# SMART4.net
KiCad netlist of a schematic drawn in EAGLE
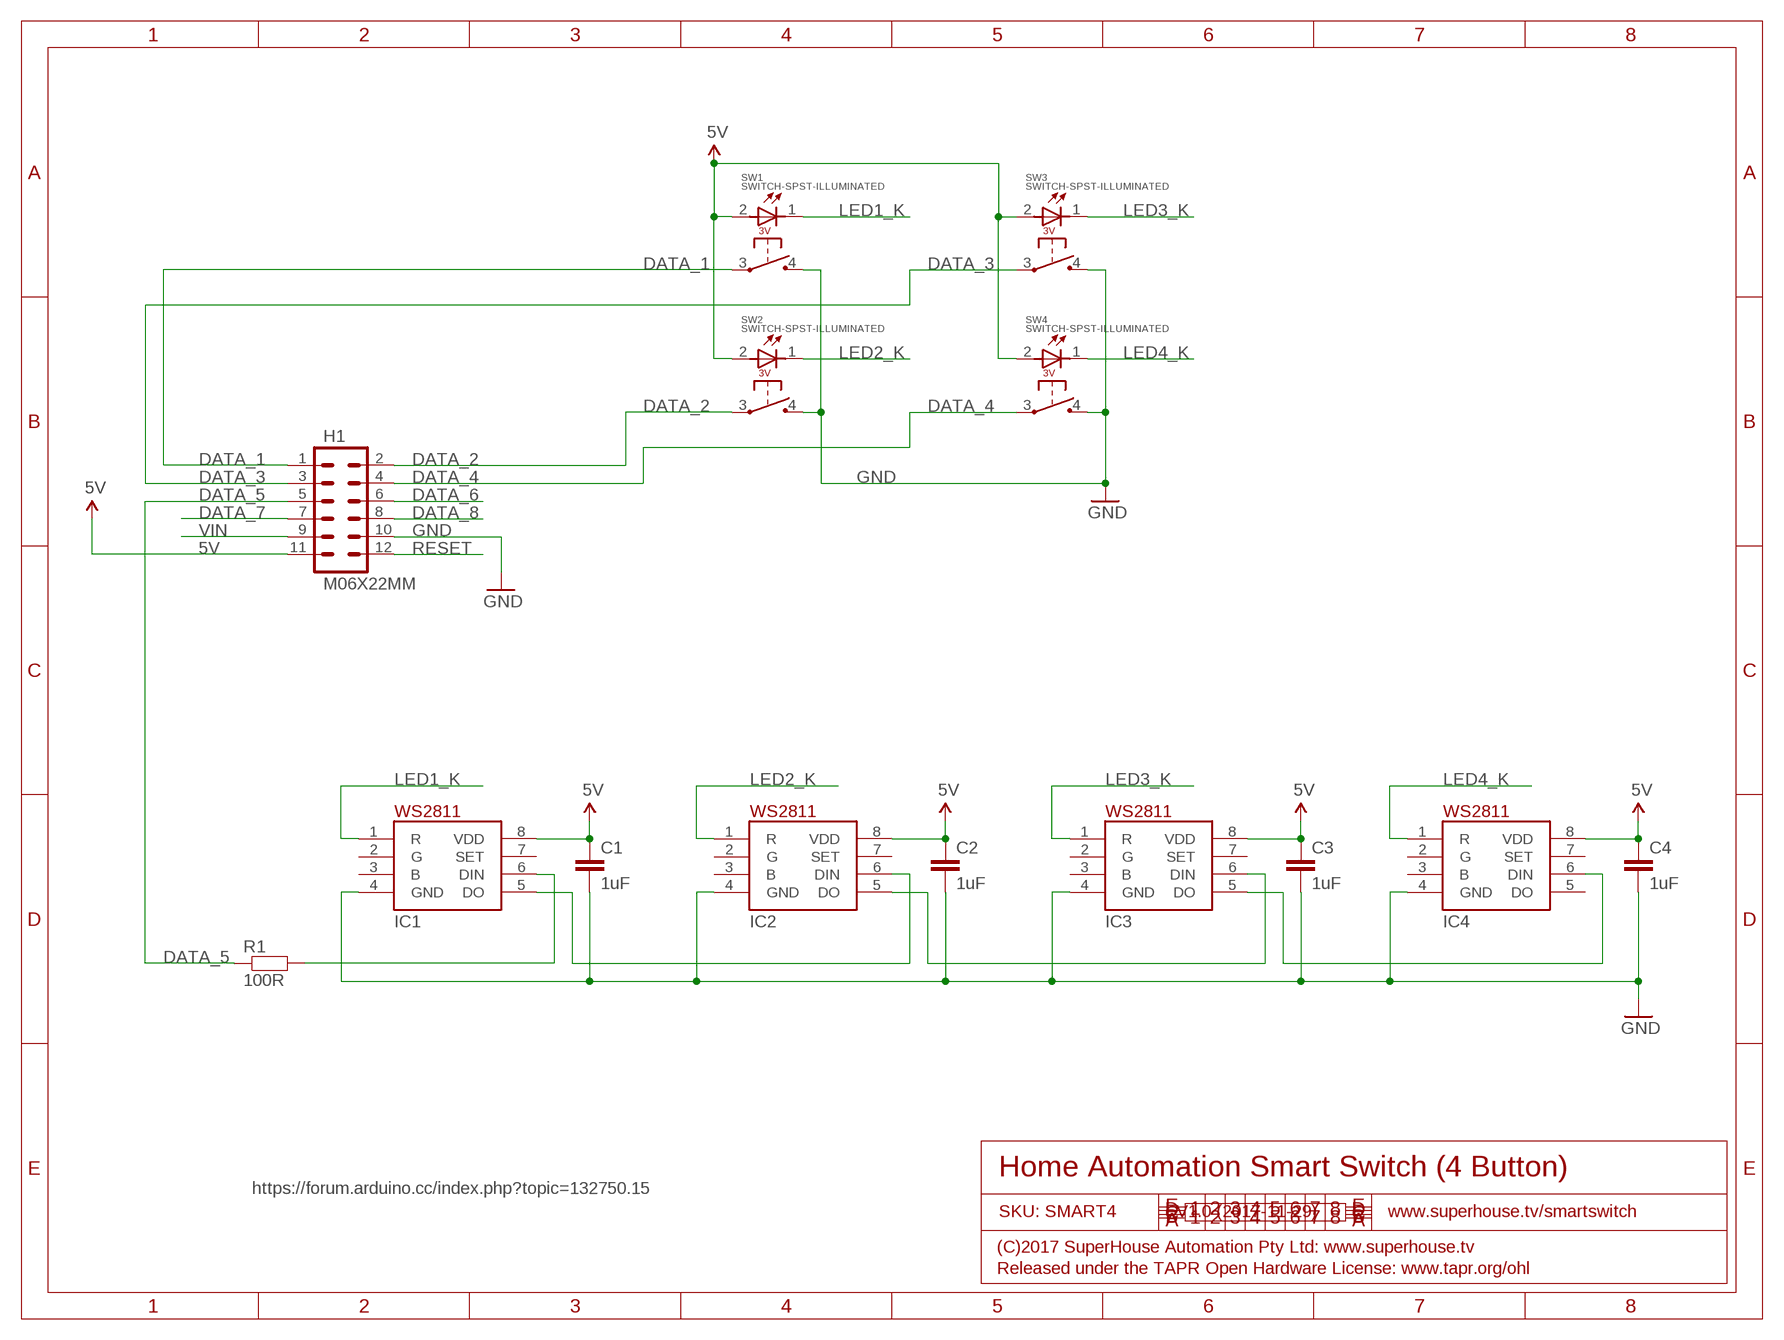
[diagram p0: schematic, sheet 1]

(export (version "E")
  (design (tool "Eeschema 10.0.6"))
  (components
    (comp (ref "C1")
      (value "1uF")
      (footprint "eagle-import:0603")
      (libsource (lib "eagle-import") (part "CAP0603"))
    )
    (comp (ref "C2")
      (value "1uF")
      (footprint "eagle-import:0603")
      (libsource (lib "eagle-import") (part "CAP0603"))
    )
    (comp (ref "C3")
      (value "1uF")
      (footprint "eagle-import:0603")
      (libsource (lib "eagle-import") (part "CAP0603"))
    )
    (comp (ref "C4")
      (value "1uF")
      (footprint "eagle-import:0603")
      (libsource (lib "eagle-import") (part "CAP0603"))
    )
    (comp (ref "H1")
      (value "M06X22MM")
      (footprint "eagle-import:2X6-2MM")
      (libsource (lib "eagle-import") (part "M06X22MM"))
    )
    (comp (ref "IC1")
      (value "WS2811-SOP8")
      (footprint "eagle-import:SO08-SKINNYPADS")
      (libsource (lib "eagle-import") (part "WS2811-SOP8"))
    )
    (comp (ref "IC2")
      (value "WS2811-SOP8")
      (footprint "eagle-import:SO08-SKINNYPADS")
      (libsource (lib "eagle-import") (part "WS2811-SOP8"))
    )
    (comp (ref "IC3")
      (value "WS2811-SOP8")
      (footprint "eagle-import:SO08-SKINNYPADS")
      (libsource (lib "eagle-import") (part "WS2811-SOP8"))
    )
    (comp (ref "IC4")
      (value "WS2811-SOP8")
      (footprint "eagle-import:SO08-SKINNYPADS")
      (libsource (lib "eagle-import") (part "WS2811-SOP8"))
    )
    (comp (ref "R1")
      (value "100R")
      (footprint "eagle-import:0603")
      (libsource (lib "eagle-import") (part "RESISTOR0603"))
    )
    (comp (ref "SW1")
      (value "SWITCH-SPST-ILLUMINATED")
      (footprint "eagle-import:SWITCH-SPST-ILLUMINATED")
      (libsource (lib "eagle-import") (part "SWITCH-SPST-ILLUMINATED"))
    )
    (comp (ref "SW2")
      (value "SWITCH-SPST-ILLUMINATED")
      (footprint "eagle-import:SWITCH-SPST-ILLUMINATED")
      (libsource (lib "eagle-import") (part "SWITCH-SPST-ILLUMINATED"))
    )
    (comp (ref "SW3")
      (value "SWITCH-SPST-ILLUMINATED")
      (footprint "eagle-import:SWITCH-SPST-ILLUMINATED")
      (libsource (lib "eagle-import") (part "SWITCH-SPST-ILLUMINATED"))
    )
    (comp (ref "SW4")
      (value "SWITCH-SPST-ILLUMINATED")
      (footprint "eagle-import:SWITCH-SPST-ILLUMINATED")
      (libsource (lib "eagle-import") (part "SWITCH-SPST-ILLUMINATED"))
    )
  )
  (nets
    (net (code "1") (name "/DATA_1") (class "Default")
      (node (ref "H1") (pin "1") (pinfunction "1_1") (pintype "passive"))
      (node (ref "SW1") (pin "3") (pinfunction "COM_3") (pintype "passive"))
    )
    (net (code "2") (name "/DATA_2") (class "Default")
      (node (ref "H1") (pin "2") (pinfunction "2_2") (pintype "passive"))
      (node (ref "SW2") (pin "3") (pinfunction "COM_3") (pintype "passive"))
    )
    (net (code "3") (name "/DATA_3") (class "Default")
      (node (ref "H1") (pin "3") (pinfunction "3_3") (pintype "passive"))
      (node (ref "SW3") (pin "3") (pinfunction "COM_3") (pintype "passive"))
    )
    (net (code "4") (name "/DATA_4") (class "Default")
      (node (ref "H1") (pin "4") (pinfunction "4_4") (pintype "passive"))
      (node (ref "SW4") (pin "3") (pinfunction "COM_3") (pintype "passive"))
    )
    (net (code "5") (name "/DATA_5") (class "Default")
      (node (ref "H1") (pin "5") (pinfunction "5_5") (pintype "passive"))
      (node (ref "R1") (pin "1") (pinfunction "1_1") (pintype "passive"))
    )
    (net (code "6") (name "/DATA_6") (class "Default")
      (node (ref "H1") (pin "6") (pinfunction "6_6") (pintype "passive"))
    )
    (net (code "7") (name "/DATA_7") (class "Default")
      (node (ref "H1") (pin "7") (pinfunction "7_7") (pintype "passive"))
    )
    (net (code "8") (name "/DATA_8") (class "Default")
      (node (ref "H1") (pin "8") (pinfunction "8_8") (pintype "passive"))
    )
    (net (code "9") (name "/LED1_K") (class "Default")
      (node (ref "IC1") (pin "1") (pinfunction "R_1") (pintype "open_collector"))
      (node (ref "SW1") (pin "1") (pinfunction "-_1") (pintype "passive"))
    )
    (net (code "10") (name "/LED2_K") (class "Default")
      (node (ref "IC2") (pin "1") (pinfunction "R_1") (pintype "open_collector"))
      (node (ref "SW2") (pin "1") (pinfunction "-_1") (pintype "passive"))
    )
    (net (code "11") (name "/LED3_K") (class "Default")
      (node (ref "IC3") (pin "1") (pinfunction "R_1") (pintype "open_collector"))
      (node (ref "SW3") (pin "1") (pinfunction "-_1") (pintype "passive"))
    )
    (net (code "12") (name "/LED4_K") (class "Default")
      (node (ref "IC4") (pin "1") (pinfunction "R_1") (pintype "open_collector"))
      (node (ref "SW4") (pin "1") (pinfunction "-_1") (pintype "passive"))
    )
    (net (code "13") (name "/RESET") (class "Default")
      (node (ref "H1") (pin "12") (pinfunction "12_12") (pintype "passive"))
    )
    (net (code "14") (name "/VIN") (class "Default")
      (node (ref "H1") (pin "9") (pinfunction "9_9") (pintype "passive"))
    )
    (net (code "15") (name "5V") (class "Default")
      (node (ref "C1") (pin "1") (pinfunction "1_1") (pintype "passive"))
      (node (ref "C2") (pin "1") (pinfunction "1_1") (pintype "passive"))
      (node (ref "C3") (pin "1") (pinfunction "1_1") (pintype "passive"))
      (node (ref "C4") (pin "1") (pinfunction "1_1") (pintype "passive"))
      (node (ref "H1") (pin "11") (pinfunction "11_11") (pintype "passive"))
      (node (ref "IC1") (pin "8") (pinfunction "VDD_8") (pintype "power_in"))
      (node (ref "IC2") (pin "8") (pinfunction "VDD_8") (pintype "power_in"))
      (node (ref "IC3") (pin "8") (pinfunction "VDD_8") (pintype "power_in"))
      (node (ref "IC4") (pin "8") (pinfunction "VDD_8") (pintype "power_in"))
      (node (ref "SW1") (pin "2") (pinfunction "+_2") (pintype "passive"))
      (node (ref "SW2") (pin "2") (pinfunction "+_2") (pintype "passive"))
      (node (ref "SW3") (pin "2") (pinfunction "+_2") (pintype "passive"))
      (node (ref "SW4") (pin "2") (pinfunction "+_2") (pintype "passive"))
    )
    (net (code "16") (name "GND") (class "Default")
      (node (ref "C1") (pin "2") (pinfunction "2_2") (pintype "passive"))
      (node (ref "C2") (pin "2") (pinfunction "2_2") (pintype "passive"))
      (node (ref "C3") (pin "2") (pinfunction "2_2") (pintype "passive"))
      (node (ref "C4") (pin "2") (pinfunction "2_2") (pintype "passive"))
      (node (ref "H1") (pin "10") (pinfunction "10_10") (pintype "passive"))
      (node (ref "IC1") (pin "4") (pinfunction "GND_4") (pintype "power_in"))
      (node (ref "IC2") (pin "4") (pinfunction "GND_4") (pintype "power_in"))
      (node (ref "IC3") (pin "4") (pinfunction "GND_4") (pintype "power_in"))
      (node (ref "IC4") (pin "4") (pinfunction "GND_4") (pintype "power_in"))
      (node (ref "SW1") (pin "4") (pinfunction "NO_4") (pintype "passive"))
      (node (ref "SW2") (pin "4") (pinfunction "NO_4") (pintype "passive"))
      (node (ref "SW3") (pin "4") (pinfunction "NO_4") (pintype "passive"))
      (node (ref "SW4") (pin "4") (pinfunction "NO_4") (pintype "passive"))
    )
    (net (code "17") (name "Net-(IC1-DIN)") (class "Default")
      (node (ref "IC1") (pin "6") (pinfunction "DIN_6") (pintype "input"))
      (node (ref "R1") (pin "2") (pinfunction "2_2") (pintype "passive"))
    )
    (net (code "18") (name "Net-(IC1-DO)") (class "Default")
      (node (ref "IC1") (pin "5") (pinfunction "DO_5") (pintype "output"))
      (node (ref "IC2") (pin "6") (pinfunction "DIN_6") (pintype "input"))
    )
    (net (code "19") (name "Net-(IC2-DO)") (class "Default")
      (node (ref "IC2") (pin "5") (pinfunction "DO_5") (pintype "output"))
      (node (ref "IC3") (pin "6") (pinfunction "DIN_6") (pintype "input"))
    )
    (net (code "20") (name "Net-(IC3-DO)") (class "Default")
      (node (ref "IC3") (pin "5") (pinfunction "DO_5") (pintype "output"))
      (node (ref "IC4") (pin "6") (pinfunction "DIN_6") (pintype "input"))
    )
    (net (code "21") (name "unconnected-(IC1-B-Pad3)") (class "Default")
      (node (ref "IC1") (pin "3") (pinfunction "B_3") (pintype "open_collector"))
    )
    (net (code "22") (name "unconnected-(IC1-G-Pad2)") (class "Default")
      (node (ref "IC1") (pin "2") (pinfunction "G_2") (pintype "open_collector"))
    )
    (net (code "23") (name "unconnected-(IC1-SET-Pad7)") (class "Default")
      (node (ref "IC1") (pin "7") (pinfunction "SET_7") (pintype "input"))
    )
    (net (code "24") (name "unconnected-(IC2-B-Pad3)") (class "Default")
      (node (ref "IC2") (pin "3") (pinfunction "B_3") (pintype "open_collector"))
    )
    (net (code "25") (name "unconnected-(IC2-G-Pad2)") (class "Default")
      (node (ref "IC2") (pin "2") (pinfunction "G_2") (pintype "open_collector"))
    )
    (net (code "26") (name "unconnected-(IC2-SET-Pad7)") (class "Default")
      (node (ref "IC2") (pin "7") (pinfunction "SET_7") (pintype "input"))
    )
    (net (code "27") (name "unconnected-(IC3-B-Pad3)") (class "Default")
      (node (ref "IC3") (pin "3") (pinfunction "B_3") (pintype "open_collector"))
    )
    (net (code "28") (name "unconnected-(IC3-G-Pad2)") (class "Default")
      (node (ref "IC3") (pin "2") (pinfunction "G_2") (pintype "open_collector"))
    )
    (net (code "29") (name "unconnected-(IC3-SET-Pad7)") (class "Default")
      (node (ref "IC3") (pin "7") (pinfunction "SET_7") (pintype "input"))
    )
    (net (code "30") (name "unconnected-(IC4-B-Pad3)") (class "Default")
      (node (ref "IC4") (pin "3") (pinfunction "B_3") (pintype "open_collector"))
    )
    (net (code "31") (name "unconnected-(IC4-DO-Pad5)") (class "Default")
      (node (ref "IC4") (pin "5") (pinfunction "DO_5") (pintype "output"))
    )
    (net (code "32") (name "unconnected-(IC4-G-Pad2)") (class "Default")
      (node (ref "IC4") (pin "2") (pinfunction "G_2") (pintype "open_collector"))
    )
    (net (code "33") (name "unconnected-(IC4-SET-Pad7)") (class "Default")
      (node (ref "IC4") (pin "7") (pinfunction "SET_7") (pintype "input"))
    )
  )
)
